# SNES_TST_Sheet2.net
KiCad netlist of a schematic drawn in Altium Designer
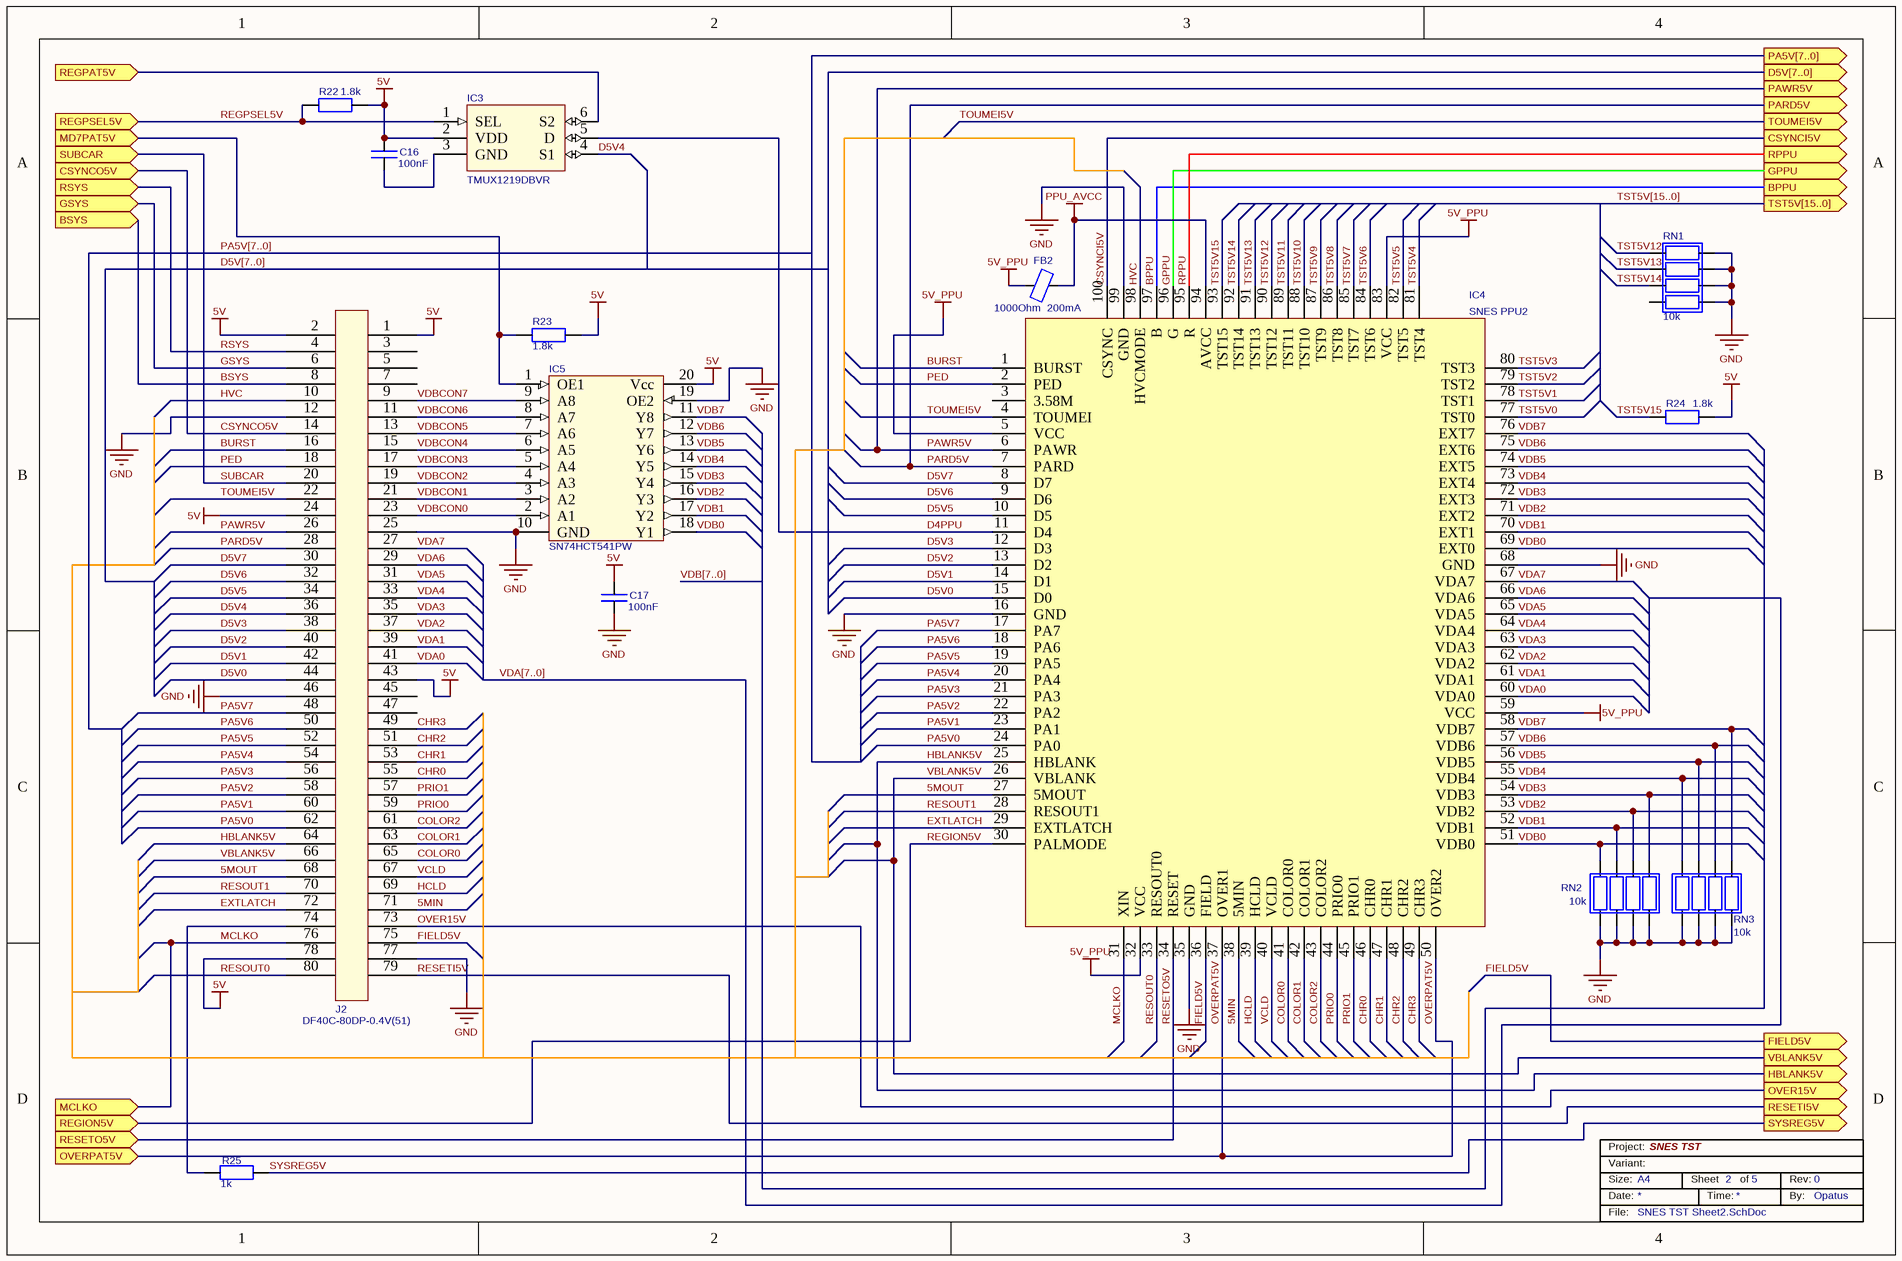
[diagram p0: SNES TST Sheet2.SchDoc]

(export (version "E")
  (design (tool "Eeschema 10.0.6"))
  (components
    (comp (ref "C16")
      (value "100nF")
      (footprint "Cap_0402_Chip")
      (fields
        (field (name "TOLERANCE") "±20%")
        (field (name "Comment") "Ceramic Capacitor 100nF 10V ±20% X7R 0402")
      )
      (libsource (lib "PCB") (part "Capacitor"))
    )
    (comp (ref "C17")
      (value "100nF")
      (footprint "Cap_0402_Chip")
      (fields
        (field (name "TOLERANCE") "±20%")
        (field (name "Comment") "Ceramic Capacitor 100nF 10V ±20% X7R 0402")
      )
      (libsource (lib "PCB") (part "Capacitor"))
    )
    (comp (ref "FB2")
      (value "1000Ohm  200mA")
      (footprint "Ind_0402_Chip")
      (fields (field (name "MANUFACTURER_PART_NUMBER") "MMZ1005S102CT000"))
      (libsource (lib "PCB") (part "Ferrite Bead"))
    )
    (comp (ref "IC3")
      (value "TMUX1219")
      (footprint "SOT23-6")
      (description "2:1 MUX")
      (fields (field (name "MANUFACTURER_PART_NUMBER") "TMUX1219DBVR"))
      (libsource (lib "PCB") (part "TMUX1219"))
    )
    (comp (ref "IC4")
      (value "SNES PPU2")
      (footprint "PPU100Pin")
      (description "PPU2")
      (libsource (lib "PCB") (part "PPU2100Pin"))
    )
    (comp (ref "IC5")
      (value "SN74HCT541")
      (footprint "TSSOP20 Narrow")
      (fields (field (name "MANUFACTURER_PART_NUMBER") "SN74HCT541PW"))
      (libsource (lib "PCB") (part "SN74HCT541"))
    )
    (comp (ref "J2")
      (value "DF40C-80DP")
      (footprint "DF40C-80DP")
      (description "80Pole Connector")
      (fields (field (name "MANUFACTURER_PART_NUMBER") "DF40C-80DP-0.4V(51)"))
      (libsource (lib "PCB") (part "Conn 80P"))
    )
    (comp (ref "R22")
      (value "1.8k")
      (footprint "Res_0402_Chip")
      (fields (field (name "TOLERANCE") "±1%") (field (name "Comment") "Resistor 1.8k 0402 ±1%"))
      (libsource (lib "PCB") (part "R"))
    )
    (comp (ref "R23")
      (value "1.8k")
      (footprint "Res_0402_Chip")
      (fields (field (name "TOLERANCE") "±1%") (field (name "Comment") "Resistor 1.8k 0402 ±1%"))
      (libsource (lib "PCB") (part "R"))
    )
    (comp (ref "R24")
      (value "1.8k")
      (footprint "Res_0402_Chip")
      (fields (field (name "TOLERANCE") "±1%") (field (name "Comment") "Resistor 1.8k 0402 ±1%"))
      (libsource (lib "PCB") (part "R"))
    )
    (comp (ref "R25")
      (value "1k")
      (footprint "Res_0402_Chip")
      (fields (field (name "TOLERANCE") "±1%") (field (name "Comment") "Resistor 1k 0402 ±1%"))
      (libsource (lib "PCB") (part "R"))
    )
    (comp (ref "RN1")
      (value "10k")
      (footprint "1206_Array_Chip")
      (fields (field (name "TOLERANCE") "±1%") (field (name "Comment") "Resistor Network 10k 1206 ±1%"))
      (libsource (lib "PCB") (part "RNetwork"))
    )
    (comp (ref "RN2")
      (value "10k")
      (footprint "1206_Array_Chip")
      (fields (field (name "TOLERANCE") "±1%") (field (name "Comment") "Resistor Network 10k 1206 ±1%"))
      (libsource (lib "") (part "RNetwork_1"))
    )
    (comp (ref "RN3")
      (value "10k")
      (footprint "1206_Array_Chip")
      (fields (field (name "TOLERANCE") "±1%") (field (name "Comment") "Resistor Network 10k 1206 ±1%"))
      (libsource (lib "") (part "RNetwork_1"))
    )
  )
  (nets
    (net (code "1") (name "/5MIN") (class "Default")
      (node (ref "IC4") (pin "38") (pinfunction "5MIN_38") (pintype "passive"))
      (node (ref "J2") (pin "71") (pintype "passive"))
    )
    (net (code "2") (name "/5MOUT") (class "Default")
      (node (ref "IC4") (pin "27") (pinfunction "5MOUT_27") (pintype "passive"))
      (node (ref "J2") (pin "68") (pintype "passive"))
    )
    (net (code "3") (name "/BPPU") (class "Default")
      (node (ref "IC4") (pin "97") (pinfunction "B_97") (pintype "passive"))
    )
    (net (code "4") (name "/BSYS") (class "Default") (node (ref "J2") (pin "8") (pintype "passive")))
    (net (code "5") (name "/BURST") (class "Default")
      (node (ref "IC4") (pin "1") (pinfunction "BURST_1") (pintype "passive"))
      (node (ref "J2") (pin "16") (pintype "passive"))
    )
    (net (code "6") (name "/CHR0") (class "Default")
      (node (ref "IC4") (pin "46") (pinfunction "CHR0_46") (pintype "passive"))
      (node (ref "J2") (pin "55") (pintype "passive"))
    )
    (net (code "7") (name "/CHR1") (class "Default")
      (node (ref "IC4") (pin "47") (pinfunction "CHR1_47") (pintype "passive"))
      (node (ref "J2") (pin "53") (pintype "passive"))
    )
    (net (code "8") (name "/CHR2") (class "Default")
      (node (ref "IC4") (pin "48") (pinfunction "CHR2_48") (pintype "passive"))
      (node (ref "J2") (pin "51") (pintype "passive"))
    )
    (net (code "9") (name "/CHR3") (class "Default")
      (node (ref "IC4") (pin "49") (pinfunction "CHR3_49") (pintype "passive"))
      (node (ref "J2") (pin "49") (pintype "passive"))
    )
    (net (code "10") (name "/COLOR0") (class "Default")
      (node (ref "IC4") (pin "41") (pinfunction "COLOR0_41") (pintype "passive"))
      (node (ref "J2") (pin "65") (pintype "passive"))
    )
    (net (code "11") (name "/COLOR1") (class "Default")
      (node (ref "IC4") (pin "42") (pinfunction "COLOR1_42") (pintype "passive"))
      (node (ref "J2") (pin "63") (pintype "passive"))
    )
    (net (code "12") (name "/COLOR2") (class "Default")
      (node (ref "IC4") (pin "43") (pinfunction "COLOR2_43") (pintype "passive"))
      (node (ref "J2") (pin "61") (pintype "passive"))
    )
    (net (code "13") (name "/CSYNCI5V") (class "Default")
      (node (ref "IC4") (pin "100") (pinfunction "CSYNC_100") (pintype "passive"))
    )
    (net (code "14") (name "/CSYNCO5V") (class "Default") (node (ref "J2") (pin "14") (pintype "passive")))
    (net (code "15") (name "/D4PPU") (class "Default")
      (node (ref "IC3") (pin "5") (pinfunction "D_5") (pintype "bidirectional"))
      (node (ref "IC4") (pin "11") (pinfunction "D4_11") (pintype "passive"))
    )
    (net (code "16") (name "/D5V0") (class "Default")
      (node (ref "IC4") (pin "15") (pinfunction "D0_15") (pintype "passive"))
      (node (ref "J2") (pin "44") (pintype "passive"))
    )
    (net (code "17") (name "/D5V1") (class "Default")
      (node (ref "IC4") (pin "14") (pinfunction "D1_14") (pintype "passive"))
      (node (ref "J2") (pin "42") (pintype "passive"))
    )
    (net (code "18") (name "/D5V2") (class "Default")
      (node (ref "IC4") (pin "13") (pinfunction "D2_13") (pintype "passive"))
      (node (ref "J2") (pin "40") (pintype "passive"))
    )
    (net (code "19") (name "/D5V3") (class "Default")
      (node (ref "IC4") (pin "12") (pinfunction "D3_12") (pintype "passive"))
      (node (ref "J2") (pin "38") (pintype "passive"))
    )
    (net (code "20") (name "/D5V4") (class "Default")
      (node (ref "IC3") (pin "4") (pinfunction "S1_4") (pintype "bidirectional"))
      (node (ref "J2") (pin "36") (pintype "passive"))
    )
    (net (code "21") (name "/D5V5") (class "Default")
      (node (ref "IC4") (pin "10") (pinfunction "D5_10") (pintype "passive"))
      (node (ref "J2") (pin "34") (pintype "passive"))
    )
    (net (code "22") (name "/D5V6") (class "Default")
      (node (ref "IC4") (pin "9") (pinfunction "D6_9") (pintype "passive"))
      (node (ref "J2") (pin "32") (pintype "passive"))
    )
    (net (code "23") (name "/D5V7") (class "Default")
      (node (ref "IC4") (pin "8") (pinfunction "D7_8") (pintype "passive"))
      (node (ref "J2") (pin "30") (pintype "passive"))
    )
    (net (code "25") (name "/EXTLATCH") (class "Default")
      (node (ref "IC4") (pin "29") (pinfunction "EXTLATCH_29") (pintype "passive"))
      (node (ref "J2") (pin "72") (pintype "passive"))
    )
    (net (code "26") (name "/FIELD5V") (class "Default")
      (node (ref "IC4") (pin "36") (pinfunction "FIELD_36") (pintype "passive"))
      (node (ref "J2") (pin "75") (pintype "passive"))
    )
    (net (code "27") (name "/GPPU") (class "Default")
      (node (ref "IC4") (pin "96") (pinfunction "G_96") (pintype "passive"))
    )
    (net (code "28") (name "/GSYS") (class "Default") (node (ref "J2") (pin "6") (pintype "passive")))
    (net (code "29") (name "/HBLANK5V") (class "Default")
      (node (ref "IC4") (pin "25") (pinfunction "HBLANK_25") (pintype "passive"))
      (node (ref "J2") (pin "64") (pintype "passive"))
    )
    (net (code "30") (name "/HCLD") (class "Default")
      (node (ref "IC4") (pin "39") (pinfunction "HCLD_39") (pintype "passive"))
      (node (ref "J2") (pin "69") (pintype "passive"))
    )
    (net (code "31") (name "/HVC") (class "Default")
      (node (ref "IC4") (pin "98") (pinfunction "HVCMODE_98") (pintype "passive"))
      (node (ref "J2") (pin "10") (pintype "passive"))
    )
    (net (code "32") (name "/MCLKO") (class "Default")
      (node (ref "IC4") (pin "31") (pinfunction "XIN_31") (pintype "passive"))
      (node (ref "J2") (pin "76") (pintype "passive"))
    )
    (net (code "33") (name "/MD7PAT5V") (class "Default")
      (node (ref "IC5") (pin "1") (pinfunction "OE1_1") (pintype "input"))
      (node (ref "R23") (pin "2") (pintype "passive"))
    )
    (net (code "34") (name "/OVER15V") (class "Default") (node (ref "J2") (pin "73") (pintype "passive")))
    (net (code "35") (name "/OVERPAT5V") (class "Default")
      (node (ref "IC4") (pin "37") (pinfunction "OVER1_37") (pintype "passive"))
      (node (ref "IC4") (pin "50") (pinfunction "OVER2_50") (pintype "passive"))
    )
    (net (code "36") (name "/PA5V0") (class "Default")
      (node (ref "IC4") (pin "24") (pinfunction "PA0_24") (pintype "passive"))
      (node (ref "J2") (pin "62") (pintype "passive"))
    )
    (net (code "37") (name "/PA5V1") (class "Default")
      (node (ref "IC4") (pin "23") (pinfunction "PA1_23") (pintype "passive"))
      (node (ref "J2") (pin "60") (pintype "passive"))
    )
    (net (code "38") (name "/PA5V2") (class "Default")
      (node (ref "IC4") (pin "22") (pinfunction "PA2_22") (pintype "passive"))
      (node (ref "J2") (pin "58") (pintype "passive"))
    )
    (net (code "39") (name "/PA5V3") (class "Default")
      (node (ref "IC4") (pin "21") (pinfunction "PA3_21") (pintype "passive"))
      (node (ref "J2") (pin "56") (pintype "passive"))
    )
    (net (code "40") (name "/PA5V4") (class "Default")
      (node (ref "IC4") (pin "20") (pinfunction "PA4_20") (pintype "passive"))
      (node (ref "J2") (pin "54") (pintype "passive"))
    )
    (net (code "41") (name "/PA5V5") (class "Default")
      (node (ref "IC4") (pin "19") (pinfunction "PA5_19") (pintype "passive"))
      (node (ref "J2") (pin "52") (pintype "passive"))
    )
    (net (code "42") (name "/PA5V6") (class "Default")
      (node (ref "IC4") (pin "18") (pinfunction "PA6_18") (pintype "passive"))
      (node (ref "J2") (pin "50") (pintype "passive"))
    )
    (net (code "43") (name "/PA5V7") (class "Default")
      (node (ref "IC4") (pin "17") (pinfunction "PA7_17") (pintype "passive"))
      (node (ref "J2") (pin "48") (pintype "passive"))
    )
    (net (code "45") (name "/PARD5V") (class "Default")
      (node (ref "IC4") (pin "7") (pinfunction "PARD_7") (pintype "passive"))
      (node (ref "J2") (pin "28") (pintype "passive"))
    )
    (net (code "46") (name "/PAWR5V") (class "Default")
      (node (ref "IC4") (pin "6") (pinfunction "PAWR_6") (pintype "passive"))
      (node (ref "J2") (pin "26") (pintype "passive"))
    )
    (net (code "47") (name "/PED") (class "Default")
      (node (ref "IC4") (pin "2") (pinfunction "PED_2") (pintype "passive"))
      (node (ref "J2") (pin "18") (pintype "passive"))
    )
    (net (code "48") (name "/PRIO0") (class "Default")
      (node (ref "IC4") (pin "44") (pinfunction "PRIO0_44") (pintype "passive"))
      (node (ref "J2") (pin "59") (pintype "passive"))
    )
    (net (code "49") (name "/PRIO1") (class "Default")
      (node (ref "IC4") (pin "45") (pinfunction "PRIO1_45") (pintype "passive"))
      (node (ref "J2") (pin "57") (pintype "passive"))
    )
    (net (code "50") (name "/REGION5V") (class "Default")
      (node (ref "IC4") (pin "30") (pinfunction "PALMODE_30") (pintype "passive"))
    )
    (net (code "51") (name "/REGPAT5V") (class "Default")
      (node (ref "IC3") (pin "6") (pinfunction "S2_6") (pintype "bidirectional"))
    )
    (net (code "52") (name "/REGPSEL5V") (class "Default")
      (node (ref "IC3") (pin "1") (pinfunction "SEL_1") (pintype "input"))
      (node (ref "R22") (pin "2") (pintype "passive"))
    )
    (net (code "53") (name "/RESETI5V") (class "Default") (node (ref "J2") (pin "79") (pintype "passive")))
    (net (code "54") (name "/RESETO5V") (class "Default")
      (node (ref "IC4") (pin "34") (pinfunction "RESET_34") (pintype "passive"))
    )
    (net (code "55") (name "/RESOUT0") (class "Default")
      (node (ref "IC4") (pin "33") (pinfunction "RESOUT0_33") (pintype "passive"))
      (node (ref "J2") (pin "80") (pintype "passive"))
    )
    (net (code "56") (name "/RESOUT1") (class "Default")
      (node (ref "IC4") (pin "28") (pinfunction "RESOUT1_28") (pintype "passive"))
      (node (ref "J2") (pin "70") (pintype "passive"))
    )
    (net (code "57") (name "/RPPU") (class "Default")
      (node (ref "IC4") (pin "95") (pinfunction "R_95") (pintype "passive"))
    )
    (net (code "58") (name "/RSYS") (class "Default") (node (ref "J2") (pin "4") (pintype "passive")))
    (net (code "59") (name "/SUBCAR") (class "Default") (node (ref "J2") (pin "20") (pintype "passive")))
    (net (code "60") (name "/SYSREG5V") (class "Default") (node (ref "R25") (pin "1") (pintype "passive")))
    (net (code "61") (name "/TOUMEI5V") (class "Default")
      (node (ref "IC4") (pin "4") (pinfunction "TOUMEI_4") (pintype "passive"))
      (node (ref "J2") (pin "22") (pintype "passive"))
    )
    (net (code "62") (name "/TST5V0") (class "Default")
      (node (ref "IC4") (pin "77") (pinfunction "TST0_77") (pintype "passive"))
    )
    (net (code "63") (name "/TST5V1") (class "Default")
      (node (ref "IC4") (pin "78") (pinfunction "TST1_78") (pintype "passive"))
    )
    (net (code "64") (name "/TST5V2") (class "Default")
      (node (ref "IC4") (pin "79") (pinfunction "TST2_79") (pintype "passive"))
    )
    (net (code "65") (name "/TST5V3") (class "Default")
      (node (ref "IC4") (pin "80") (pinfunction "TST3_80") (pintype "passive"))
    )
    (net (code "66") (name "/TST5V4") (class "Default")
      (node (ref "IC4") (pin "81") (pinfunction "TST4_81") (pintype "passive"))
    )
    (net (code "67") (name "/TST5V5") (class "Default")
      (node (ref "IC4") (pin "82") (pinfunction "TST5_82") (pintype "passive"))
    )
    (net (code "68") (name "/TST5V6") (class "Default")
      (node (ref "IC4") (pin "84") (pinfunction "TST6_84") (pintype "passive"))
    )
    (net (code "69") (name "/TST5V7") (class "Default")
      (node (ref "IC4") (pin "85") (pinfunction "TST7_85") (pintype "passive"))
    )
    (net (code "70") (name "/TST5V8") (class "Default")
      (node (ref "IC4") (pin "86") (pinfunction "TST8_86") (pintype "passive"))
    )
    (net (code "71") (name "/TST5V9") (class "Default")
      (node (ref "IC4") (pin "87") (pinfunction "TST9_87") (pintype "passive"))
    )
    (net (code "72") (name "/TST5V10") (class "Default")
      (node (ref "IC4") (pin "88") (pinfunction "TST10_88") (pintype "passive"))
    )
    (net (code "73") (name "/TST5V11") (class "Default")
      (node (ref "IC4") (pin "89") (pinfunction "TST11_89") (pintype "passive"))
    )
    (net (code "74") (name "/TST5V12") (class "Default")
      (node (ref "IC4") (pin "90") (pinfunction "TST12_90") (pintype "passive"))
      (node (ref "RN1") (pin "5") (pintype "passive"))
    )
    (net (code "75") (name "/TST5V13") (class "Default")
      (node (ref "IC4") (pin "91") (pinfunction "TST13_91") (pintype "passive"))
      (node (ref "RN1") (pin "6") (pintype "passive"))
    )
    (net (code "76") (name "/TST5V14") (class "Default")
      (node (ref "IC4") (pin "92") (pinfunction "TST14_92") (pintype "passive"))
      (node (ref "RN1") (pin "7") (pintype "passive"))
    )
    (net (code "77") (name "/TST5V15") (class "Default")
      (node (ref "IC4") (pin "93") (pinfunction "TST15_93") (pintype "passive"))
      (node (ref "R24") (pin "2") (pintype "passive"))
    )
    (net (code "79") (name "/VBLANK5V") (class "Default")
      (node (ref "IC4") (pin "26") (pinfunction "VBLANK_26") (pintype "passive"))
      (node (ref "J2") (pin "66") (pintype "passive"))
    )
    (net (code "80") (name "/VCLD") (class "Default")
      (node (ref "IC4") (pin "40") (pinfunction "VCLD_40") (pintype "passive"))
      (node (ref "J2") (pin "67") (pintype "passive"))
    )
    (net (code "81") (name "/VDA0") (class "Default")
      (node (ref "IC4") (pin "60") (pinfunction "VDA0_60") (pintype "passive"))
      (node (ref "J2") (pin "41") (pintype "passive"))
    )
    (net (code "82") (name "/VDA1") (class "Default")
      (node (ref "IC4") (pin "61") (pinfunction "VDA1_61") (pintype "passive"))
      (node (ref "J2") (pin "39") (pintype "passive"))
    )
    (net (code "83") (name "/VDA2") (class "Default")
      (node (ref "IC4") (pin "62") (pinfunction "VDA2_62") (pintype "passive"))
      (node (ref "J2") (pin "37") (pintype "passive"))
    )
    (net (code "84") (name "/VDA3") (class "Default")
      (node (ref "IC4") (pin "63") (pinfunction "VDA3_63") (pintype "passive"))
      (node (ref "J2") (pin "35") (pintype "passive"))
    )
    (net (code "85") (name "/VDA4") (class "Default")
      (node (ref "IC4") (pin "64") (pinfunction "VDA4_64") (pintype "passive"))
      (node (ref "J2") (pin "33") (pintype "passive"))
    )
    (net (code "86") (name "/VDA5") (class "Default")
      (node (ref "IC4") (pin "65") (pinfunction "VDA5_65") (pintype "passive"))
      (node (ref "J2") (pin "31") (pintype "passive"))
    )
    (net (code "87") (name "/VDA6") (class "Default")
      (node (ref "IC4") (pin "66") (pinfunction "VDA6_66") (pintype "passive"))
      (node (ref "J2") (pin "29") (pintype "passive"))
    )
    (net (code "88") (name "/VDA7") (class "Default")
      (node (ref "IC4") (pin "67") (pinfunction "VDA7_67") (pintype "passive"))
      (node (ref "J2") (pin "27") (pintype "passive"))
    )
    (net (code "90") (name "/VDB0") (class "Default")
      (node (ref "IC4") (pin "51") (pinfunction "VDB0_51") (pintype "passive"))
      (node (ref "IC4") (pin "69") (pinfunction "EXT0_69") (pintype "passive"))
      (node (ref "IC5") (pin "18") (pinfunction "Y1_18") (pintype "output"))
      (node (ref "RN2") (pin "8") (pintype "passive"))
    )
    (net (code "91") (name "/VDB1") (class "Default")
      (node (ref "IC4") (pin "52") (pinfunction "VDB1_52") (pintype "passive"))
      (node (ref "IC4") (pin "70") (pinfunction "EXT1_70") (pintype "passive"))
      (node (ref "IC5") (pin "17") (pinfunction "Y2_17") (pintype "output"))
      (node (ref "RN2") (pin "7") (pintype "passive"))
    )
    (net (code "92") (name "/VDB2") (class "Default")
      (node (ref "IC4") (pin "53") (pinfunction "VDB2_53") (pintype "passive"))
      (node (ref "IC4") (pin "71") (pinfunction "EXT2_71") (pintype "passive"))
      (node (ref "IC5") (pin "16") (pinfunction "Y3_16") (pintype "output"))
      (node (ref "RN2") (pin "6") (pintype "passive"))
    )
    (net (code "93") (name "/VDB3") (class "Default")
      (node (ref "IC4") (pin "54") (pinfunction "VDB3_54") (pintype "passive"))
      (node (ref "IC4") (pin "72") (pinfunction "EXT3_72") (pintype "passive"))
      (node (ref "IC5") (pin "15") (pinfunction "Y4_15") (pintype "output"))
      (node (ref "RN2") (pin "5") (pintype "passive"))
    )
    (net (code "94") (name "/VDB4") (class "Default")
      (node (ref "IC4") (pin "55") (pinfunction "VDB4_55") (pintype "passive"))
      (node (ref "IC4") (pin "73") (pinfunction "EXT4_73") (pintype "passive"))
      (node (ref "IC5") (pin "14") (pinfunction "Y5_14") (pintype "output"))
      (node (ref "RN3") (pin "8") (pintype "passive"))
    )
    (net (code "95") (name "/VDB5") (class "Default")
      (node (ref "IC4") (pin "56") (pinfunction "VDB5_56") (pintype "passive"))
      (node (ref "IC4") (pin "74") (pinfunction "EXT5_74") (pintype "passive"))
      (node (ref "IC5") (pin "13") (pinfunction "Y6_13") (pintype "output"))
      (node (ref "RN3") (pin "7") (pintype "passive"))
    )
    (net (code "96") (name "/VDB6") (class "Default")
      (node (ref "IC4") (pin "57") (pinfunction "VDB6_57") (pintype "passive"))
      (node (ref "IC4") (pin "75") (pinfunction "EXT6_75") (pintype "passive"))
      (node (ref "IC5") (pin "12") (pinfunction "Y7_12") (pintype "output"))
      (node (ref "RN3") (pin "6") (pintype "passive"))
    )
    (net (code "97") (name "/VDB7") (class "Default")
      (node (ref "IC4") (pin "58") (pinfunction "VDB7_58") (pintype "passive"))
      (node (ref "IC4") (pin "76") (pinfunction "EXT7_76") (pintype "passive"))
      (node (ref "IC5") (pin "11") (pinfunction "Y8_11") (pintype "output"))
      (node (ref "RN3") (pin "5") (pintype "passive"))
    )
    (net (code "98") (name "/VDBCON0") (class "Default")
      (node (ref "IC5") (pin "2") (pinfunction "A1_2") (pintype "input"))
      (node (ref "J2") (pin "23") (pintype "passive"))
    )
    (net (code "99") (name "/VDBCON1") (class "Default")
      (node (ref "IC5") (pin "3") (pinfunction "A2_3") (pintype "input"))
      (node (ref "J2") (pin "21") (pintype "passive"))
    )
    (net (code "100") (name "/VDBCON2") (class "Default")
      (node (ref "IC5") (pin "4") (pinfunction "A3_4") (pintype "input"))
      (node (ref "J2") (pin "19") (pintype "passive"))
    )
    (net (code "101") (name "/VDBCON3") (class "Default")
      (node (ref "IC5") (pin "5") (pinfunction "A4_5") (pintype "input"))
      (node (ref "J2") (pin "17") (pintype "passive"))
    )
    (net (code "102") (name "/VDBCON4") (class "Default")
      (node (ref "IC5") (pin "6") (pinfunction "A5_6") (pintype "input"))
      (node (ref "J2") (pin "15") (pintype "passive"))
    )
    (net (code "103") (name "/VDBCON5") (class "Default")
      (node (ref "IC5") (pin "7") (pinfunction "A6_7") (pintype "input"))
      (node (ref "J2") (pin "13") (pintype "passive"))
    )
    (net (code "104") (name "/VDBCON6") (class "Default")
      (node (ref "IC5") (pin "8") (pinfunction "A7_8") (pintype "input"))
      (node (ref "J2") (pin "11") (pintype "passive"))
    )
    (net (code "105") (name "/VDBCON7") (class "Default")
      (node (ref "IC5") (pin "9") (pinfunction "A8_9") (pintype "input"))
      (node (ref "J2") (pin "9") (pintype "passive"))
    )
    (net (code "107") (name "5V") (class "Default")
      (node (ref "C16") (pin "1") (pintype "passive"))
      (node (ref "C17") (pin "1") (pintype "passive"))
      (node (ref "IC3") (pin "2") (pinfunction "VDD_2") (pintype "power_in"))
      (node (ref "IC5") (pin "20") (pinfunction "Vcc_20") (pintype "power_in"))
      (node (ref "J2") (pin "1") (pintype "passive"))
      (node (ref "J2") (pin "2") (pintype "passive"))
      (node (ref "J2") (pin "24") (pintype "passive"))
      (node (ref "J2") (pin "43") (pintype "passive"))
      (node (ref "J2") (pin "78") (pintype "passive"))
      (node (ref "R22") (pin "1") (pintype "passive"))
      (node (ref "R23") (pin "1") (pintype "passive"))
      (node (ref "R24") (pin "1") (pintype "passive"))
    )
    (net (code "108") (name "5V_PPU") (class "Default")
      (node (ref "FB2") (pin "1") (pintype "passive"))
      (node (ref "IC4") (pin "32") (pinfunction "VCC_32") (pintype "passive"))
      (node (ref "IC4") (pin "5") (pinfunction "VCC_5") (pintype "passive"))
      (node (ref "IC4") (pin "59") (pinfunction "VCC_59") (pintype "passive"))
      (node (ref "IC4") (pin "83") (pinfunction "VCC_83") (pintype "passive"))
    )
    (net (code "109") (name "GND") (class "Default")
      (node (ref "C17") (pin "2") (pintype "passive"))
      (node (ref "IC4") (pin "16") (pinfunction "GND_16") (pintype "passive"))
      (node (ref "IC4") (pin "35") (pinfunction "GND_35") (pintype "passive"))
      (node (ref "IC4") (pin "68") (pinfunction "GND_68") (pintype "passive"))
      (node (ref "IC4") (pin "99") (pinfunction "GND_99") (pintype "passive"))
      (node (ref "IC5") (pin "10") (pinfunction "GND_10") (pintype "power_in"))
      (node (ref "IC5") (pin "19") (pinfunction "OE2_19") (pintype "input"))
      (node (ref "J2") (pin "12") (pintype "passive"))
      (node (ref "J2") (pin "25") (pintype "passive"))
      (node (ref "J2") (pin "46") (pintype "passive"))
      (node (ref "J2") (pin "77") (pintype "passive"))
      (node (ref "RN1") (pin "1") (pintype "passive"))
      (node (ref "RN1") (pin "2") (pintype "passive"))
      (node (ref "RN1") (pin "3") (pintype "passive"))
      (node (ref "RN1") (pin "4") (pintype "passive"))
      (node (ref "RN2") (pin "1") (pintype "passive"))
      (node (ref "RN2") (pin "2") (pintype "passive"))
      (node (ref "RN2") (pin "3") (pintype "passive"))
      (node (ref "RN2") (pin "4") (pintype "passive"))
      (node (ref "RN3") (pin "1") (pintype "passive"))
      (node (ref "RN3") (pin "2") (pintype "passive"))
      (node (ref "RN3") (pin "3") (pintype "passive"))
      (node (ref "RN3") (pin "4") (pintype "passive"))
    )
    (net (code "110") (name "Net-(IC3-GND)") (class "Default")
      (node (ref "C16") (pin "2") (pintype "passive"))
      (node (ref "IC3") (pin "3") (pinfunction "GND_3") (pintype "power_in"))
    )
    (net (code "111") (name "Net-(J2-Pad74)") (class "Default")
      (node (ref "J2") (pin "74") (pintype "passive"))
      (node (ref "R25") (pin "2") (pintype "passive"))
    )
    (net (code "112") (name "PPU_AVCC") (class "Default")
      (node (ref "FB2") (pin "2") (pintype "passive"))
      (node (ref "IC4") (pin "94") (pinfunction "AVCC_94") (pintype "passive"))
    )
    (net (code "113") (name "unconnected-(IC4-3.58M-Pad3)") (class "Default")
      (node (ref "IC4") (pin "3") (pinfunction "3.58M_3") (pintype "passive"))
    )
    (net (code "114") (name "unconnected-(J2-Pad3)") (class "Default")
      (node (ref "J2") (pin "3") (pintype "passive"))
    )
    (net (code "115") (name "unconnected-(J2-Pad5)") (class "Default")
      (node (ref "J2") (pin "5") (pintype "passive"))
    )
    (net (code "116") (name "unconnected-(J2-Pad7)") (class "Default")
      (node (ref "J2") (pin "7") (pintype "passive"))
    )
    (net (code "117") (name "unconnected-(J2-Pad45)") (class "Default")
      (node (ref "J2") (pin "45") (pintype "passive"))
    )
    (net (code "118") (name "unconnected-(J2-Pad47)") (class "Default")
      (node (ref "J2") (pin "47") (pintype "passive"))
    )
    (net (code "119") (name "unconnected-(RN1-Pad8)") (class "Default")
      (node (ref "RN1") (pin "8") (pintype "passive"))
    )
  )
)
